# schematics.net
KiCad netlist of a schematic drawn in EAGLE
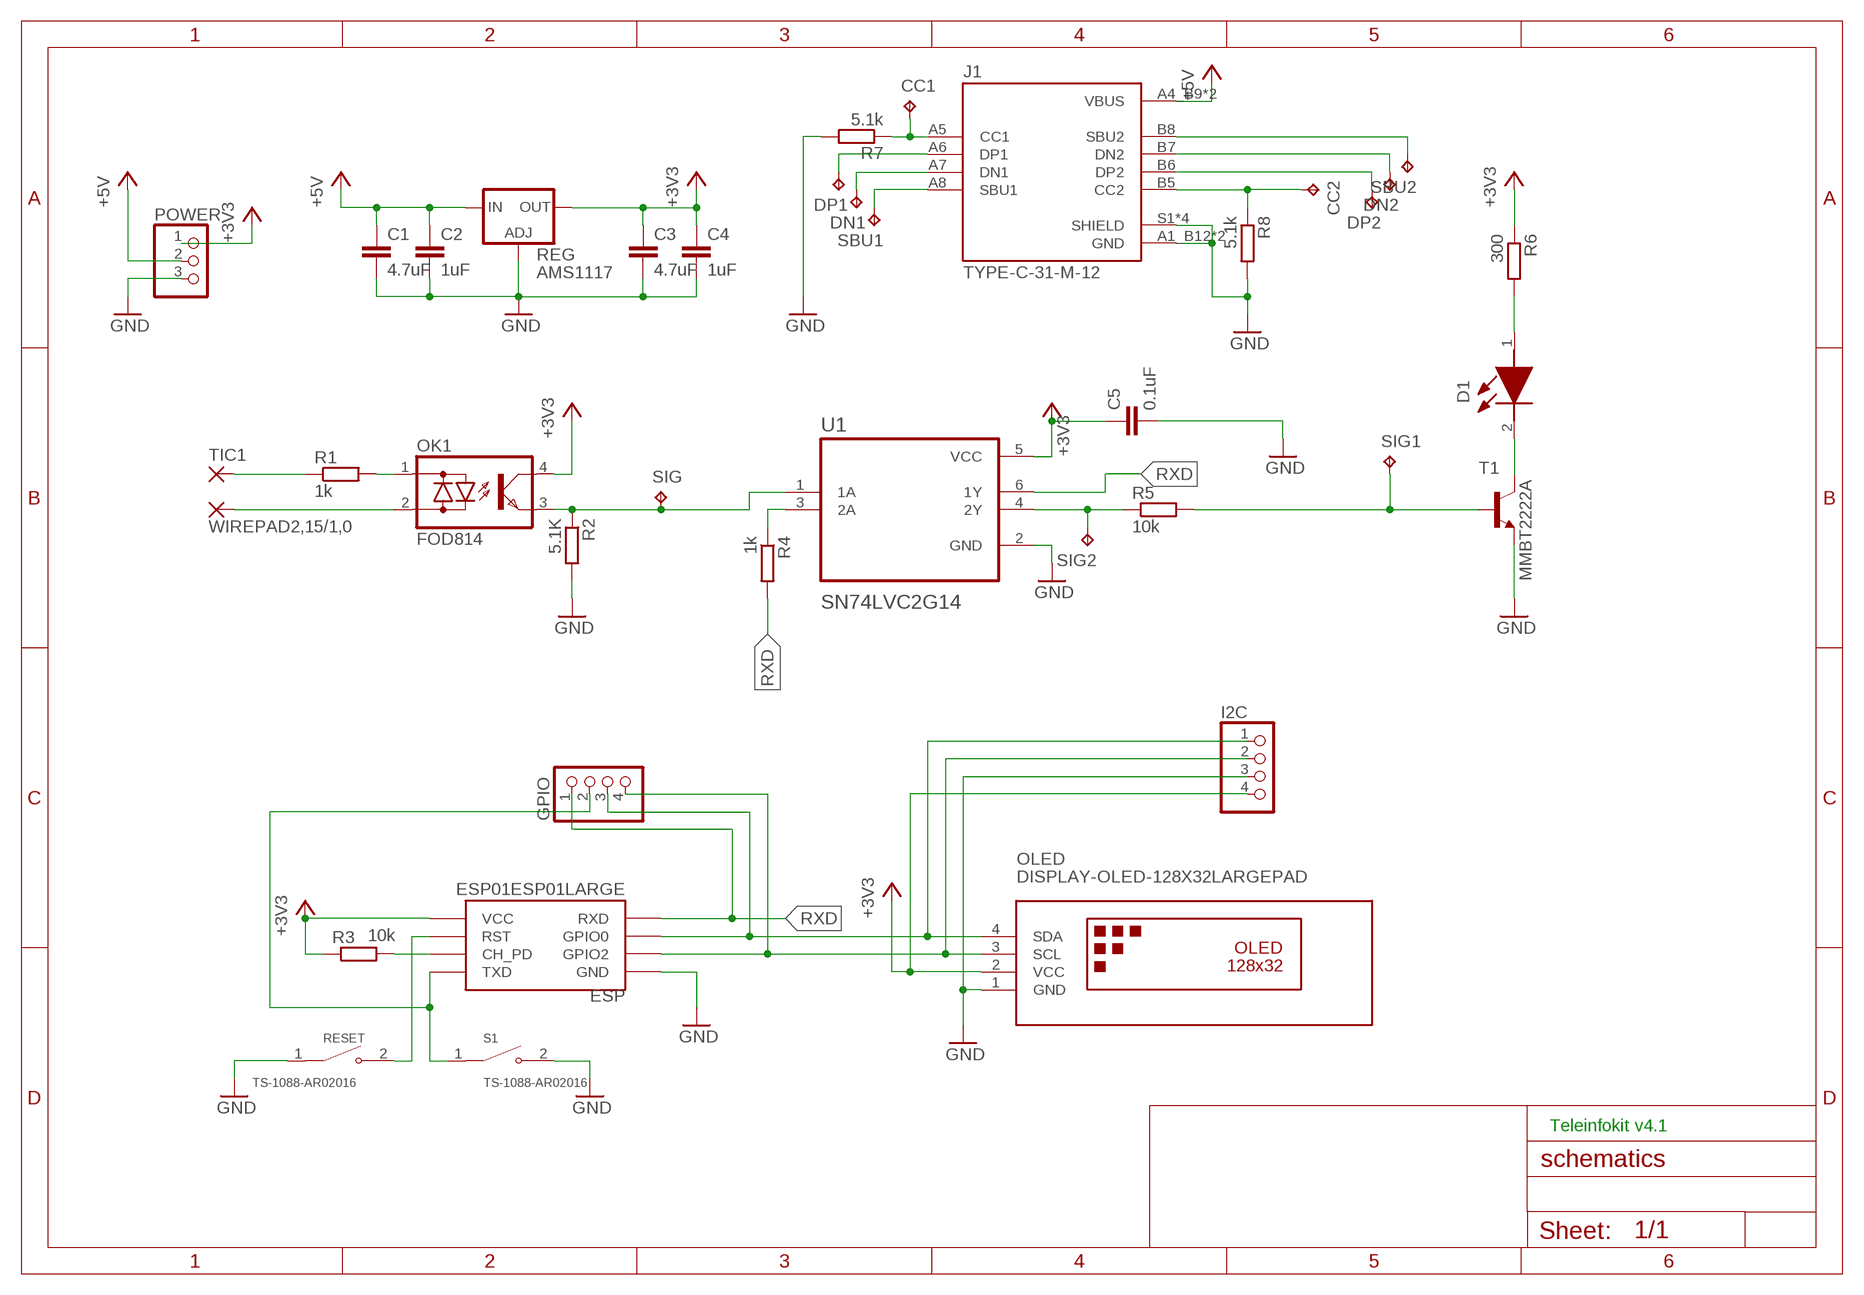
[diagram p0: schematic, sheet 1]

(export (version "E")
  (design (tool "Eeschema 10.0.6"))
  (components
    (comp (ref "C1")
      (value "4.7uF")
      (footprint "eagle-import:C0805")
      (fields (field (name "LCSC_PART") "C1779"))
      (libsource (lib "eagle-import") (part "C-EUC0805"))
    )
    (comp (ref "C2")
      (value "1uF")
      (footprint "eagle-import:C0805")
      (fields (field (name "LCSC_PART") "C28323"))
      (libsource (lib "eagle-import") (part "C-EUC0805"))
    )
    (comp (ref "C3")
      (value "4.7uF")
      (footprint "eagle-import:C0805")
      (fields (field (name "LCSC_PART") "C1779"))
      (libsource (lib "eagle-import") (part "C-EUC0805"))
    )
    (comp (ref "C4")
      (value "1uF")
      (footprint "eagle-import:C0805")
      (fields (field (name "LCSC_PART") "C28323"))
      (libsource (lib "eagle-import") (part "C-EUC0805"))
    )
    (comp (ref "C5")
      (value "0.1uF")
      (footprint "eagle-import:C0402K")
      (fields (field (name "LCSC_PART") "C1525"))
      (libsource (lib "eagle-import") (part "C-EUC0402K"))
    )
    (comp (ref "CC1")
      (value "TPB1,27")
      (footprint "eagle-import:B1,27")
      (libsource (lib "eagle-import") (part "TPB1,27"))
    )
    (comp (ref "CC2")
      (value "TPB1,27")
      (footprint "eagle-import:B1,27")
      (libsource (lib "eagle-import") (part "TPB1,27"))
    )
    (comp (ref "D1")
      (value "17-21SURC_S530-A2_TR8")
      (footprint "eagle-import:1721SURCS530A2TR8")
      (fields (field (name "ARROW_PART_NUMBER") "17-21SURC/S530-A2/TR8"))
      (libsource (lib "eagle-import") (part "17-21SURC_S530-A2_TR8"))
    )
    (comp (ref "DN1")
      (value "TPB1,27")
      (footprint "eagle-import:B1,27")
      (libsource (lib "eagle-import") (part "TPB1,27"))
    )
    (comp (ref "DN2")
      (value "TPB1,27")
      (footprint "eagle-import:B1,27")
      (libsource (lib "eagle-import") (part "TPB1,27"))
    )
    (comp (ref "DP1")
      (value "TPB1,27")
      (footprint "eagle-import:B1,27")
      (libsource (lib "eagle-import") (part "TPB1,27"))
    )
    (comp (ref "DP2")
      (value "TPB1,27")
      (footprint "eagle-import:B1,27")
      (libsource (lib "eagle-import") (part "TPB1,27"))
    )
    (comp (ref "ESP")
      (value "ESP01ESP01LARGE")
      (footprint "eagle-import:ESP01LARGE")
      (fields (field (name "LCSC_PART") "C2935984"))
      (libsource (lib "eagle-import") (part "ESP01ESP01LARGE"))
    )
    (comp (ref "GPIO")
      (value "PINHD-1X4")
      (footprint "eagle-import:1X04")
      (libsource (lib "eagle-import") (part "pinhead_325_PINHD-1X4"))
    )
    (comp (ref "I2C")
      (value "PINHD-1X4ROUNDLARGE")
      (footprint "eagle-import:1X04ROUNDLARGE")
      (libsource (lib "eagle-import") (part "PINHD-1X4ROUNDLARGE"))
    )
    (comp (ref "J1")
      (value "TYPE-C-31-M-12")
      (footprint "eagle-import:HRO_TYPE-C-31-M-12")
      (fields (field (name "MF") "HRO Electronics Co., Ltd.") (field (name "LCSC_PART") "C165948"))
      (libsource (lib "eagle-import") (part "TYPE-C-31-M-12"))
    )
    (comp (ref "OK1")
      (value "FOD814")
      (footprint "eagle-import:DIL4-SMD")
      (fields
        (field (name "MF") "VISHAY/TELEFUNKEN")
        (field (name "MPN") "SFH6206-3")
        (field (name "LCSC_PART") "C479718")
      )
      (libsource (lib "eagle-import") (part "SFH6206"))
    )
    (comp (ref "OLED")
      (value "DISPLAY-OLED-128X32LARGEPAD")
      (footprint "eagle-import:DISPLAY-OLED-128X32LARGE")
      (fields (field (name "LCSC_PART") "C2718488"))
      (libsource (lib "eagle-import") (part "DISPLAY-OLED-128X32LARGEPAD"))
    )
    (comp (ref "POWER")
      (value "PINHD-1X3")
      (footprint "eagle-import:1X03")
      (libsource (lib "eagle-import") (part "PINHD-1X3"))
    )
    (comp (ref "R1")
      (value "1k")
      (footprint "eagle-import:R0805")
      (fields (field (name "LCSC_PART") "C17513"))
      (libsource (lib "eagle-import") (part "R-EU_R0805"))
    )
    (comp (ref "R2")
      (value "5.1K")
      (footprint "eagle-import:R0603")
      (fields (field (name "LCSC_PART") "C23186"))
      (libsource (lib "eagle-import") (part "R-EU_R0603"))
    )
    (comp (ref "R3")
      (value "10k")
      (footprint "eagle-import:R0805")
      (fields (field (name "LCSC_PART") "C17414"))
      (libsource (lib "eagle-import") (part "R-EU_R0805"))
    )
    (comp (ref "R4")
      (value "1k")
      (footprint "eagle-import:R0805")
      (fields (field (name "LCSC_PART") "C17414"))
      (libsource (lib "eagle-import") (part "R-EU_R0805"))
    )
    (comp (ref "R5")
      (value "10k")
      (footprint "eagle-import:R0805")
      (fields (field (name "LCSC_PART") "C17414"))
      (libsource (lib "eagle-import") (part "R-EU_R0805"))
    )
    (comp (ref "R6")
      (value "300")
      (footprint "eagle-import:R0805")
      (fields (field (name "LCSC_PART") "C17617"))
      (libsource (lib "eagle-import") (part "R-EU_R0805"))
    )
    (comp (ref "R7")
      (value "5.1k")
      (footprint "eagle-import:R0402")
      (fields (field (name "LCSC_PART") "C25905"))
      (libsource (lib "eagle-import") (part "R-EU_R0402"))
    )
    (comp (ref "R8")
      (value "5.1k")
      (footprint "eagle-import:R0402")
      (fields (field (name "LCSC_PART") "C25905"))
      (libsource (lib "eagle-import") (part "R-EU_R0402"))
    )
    (comp (ref "REG")
      (value "AMS1117")
      (footprint "eagle-import:SOT223")
      (fields (field (name "LCSC_PART") "C6186"))
      (libsource (lib "eagle-import") (part "LD117A?S33TR"))
    )
    (comp (ref "RESET")
      (value "TS-1088-AR02016")
      (footprint "eagle-import:SW_TS-1088-AR02016")
      (fields (field (name "MF") "Xunpu") (field (name "LCSC_PART") "C720477"))
      (libsource (lib "eagle-import") (part "TS-1088-AR02016"))
    )
    (comp (ref "S1")
      (value "TS-1088-AR02016")
      (footprint "eagle-import:SW_TS-1088-AR02016")
      (fields (field (name "MF") "Xunpu") (field (name "LCSC_PART") "C720477"))
      (libsource (lib "eagle-import") (part "TS-1088-AR02016"))
    )
    (comp (ref "SBU1")
      (value "TPB1,27")
      (footprint "eagle-import:B1,27")
      (libsource (lib "eagle-import") (part "TPB1,27"))
    )
    (comp (ref "SBU2")
      (value "TPB1,27")
      (footprint "eagle-import:B1,27")
      (libsource (lib "eagle-import") (part "TPB1,27"))
    )
    (comp (ref "SIG")
      (value "TPB1,27")
      (footprint "eagle-import:B1,27")
      (libsource (lib "eagle-import") (part "TPB1,27"))
    )
    (comp (ref "SIG1")
      (value "TPB1,27")
      (footprint "eagle-import:B1,27")
      (libsource (lib "eagle-import") (part "TPB1,27"))
    )
    (comp (ref "SIG2")
      (value "TPB1,27")
      (footprint "eagle-import:B1,27")
      (libsource (lib "eagle-import") (part "TPB1,27"))
    )
    (comp (ref "T1")
      (value "MMBT2222A")
      (footprint "eagle-import:SOT23-BEC")
      (fields (field (name "LCSC_PART") "C8512"))
      (libsource (lib "eagle-import") (part "-NPN-SOT23-BECMMBT2222ALT1"))
    )
    (comp (ref "TIC1")
      (value "WIREPAD2,15/1,0")
      (footprint "eagle-import:2,15_1,0")
      (libsource (lib "eagle-import") (part "WIREPAD2,15/1,0"))
    )
    (comp (ref "TIC2")
      (value "WIREPAD2,15/1,0")
      (footprint "eagle-import:2,15_1,0")
      (libsource (lib "eagle-import") (part "WIREPAD2,15/1,0"))
    )
    (comp (ref "U1")
      (value "SN74LVC2G14")
      (footprint "eagle-import:SOT95P280X145-6N")
      (fields
        (field (name "MF") "Texas Instruments")
        (field (name "MP") "SN74LVC2G14DBVR")
        (field (name "LCSC_PART") "C12401")
      )
      (libsource (lib "eagle-import") (part "SN74LVC2G14DBVR"))
    )
  )
  (nets
    (net (code "1") (name "+3V3") (class "Default")
      (node (ref "C3") (pin "1") (pinfunction "1_1") (pintype "passive"))
      (node (ref "C4") (pin "1") (pinfunction "1_1") (pintype "passive"))
      (node (ref "C5") (pin "1") (pinfunction "1_1") (pintype "passive"))
      (node (ref "ESP") (pin "VCC") (pinfunction "VCC_VCC") (pintype "bidirectional"))
      (node (ref "I2C") (pin "4") (pinfunction "4_4") (pintype "passive"))
      (node (ref "OK1") (pin "4") (pinfunction "C_4") (pintype "passive"))
      (node (ref "OLED") (pin "2") (pinfunction "VCC_2") (pintype "power_in"))
      (node (ref "POWER") (pin "1") (pinfunction "1_1") (pintype "passive"))
      (node (ref "R3") (pin "1") (pinfunction "1_1") (pintype "passive"))
      (node (ref "R6") (pin "1") (pinfunction "1_1") (pintype "passive"))
      (node (ref "REG") (pin "4") (pinfunction "OUT_4") (pintype "passive"))
      (node (ref "U1") (pin "5") (pinfunction "VCC_5") (pintype "power_in"))
    )
    (net (code "2") (name "+5V") (class "Default")
      (node (ref "C1") (pin "1") (pinfunction "1_1") (pintype "passive"))
      (node (ref "C2") (pin "1") (pinfunction "1_1") (pintype "passive"))
      (node (ref "J1") (pin "A4_B9") (pinfunction "VBUS_A4_B9") (pintype "power_in"))
      (node (ref "J1") (pin "B4_A9") (pinfunction "VBUS_B4_A9") (pintype "power_in"))
      (node (ref "POWER") (pin "2") (pinfunction "2_2") (pintype "passive"))
      (node (ref "REG") (pin "3") (pinfunction "IN_3") (pintype "input"))
    )
    (net (code "3") (name "GND") (class "Default")
      (node (ref "C1") (pin "2") (pinfunction "2_2") (pintype "passive"))
      (node (ref "C2") (pin "2") (pinfunction "2_2") (pintype "passive"))
      (node (ref "C3") (pin "2") (pinfunction "2_2") (pintype "passive"))
      (node (ref "C4") (pin "2") (pinfunction "2_2") (pintype "passive"))
      (node (ref "C5") (pin "2") (pinfunction "2_2") (pintype "passive"))
      (node (ref "ESP") (pin "GND") (pinfunction "GND_GND") (pintype "bidirectional"))
      (node (ref "I2C") (pin "3") (pinfunction "3_3") (pintype "passive"))
      (node (ref "J1") (pin "A1_B12") (pinfunction "GND_A1_B12") (pintype "power_in"))
      (node (ref "J1") (pin "B1_A12") (pinfunction "GND_B1_A12") (pintype "power_in"))
      (node (ref "J1") (pin "S1") (pinfunction "SHIELD_S1") (pintype "passive"))
      (node (ref "J1") (pin "S2") (pinfunction "SHIELD_S2") (pintype "passive"))
      (node (ref "J1") (pin "S3") (pinfunction "SHIELD_S3") (pintype "passive"))
      (node (ref "J1") (pin "S4") (pinfunction "SHIELD_S4") (pintype "passive"))
      (node (ref "OLED") (pin "1") (pinfunction "GND_1") (pintype "power_in"))
      (node (ref "POWER") (pin "3") (pinfunction "3_3") (pintype "passive"))
      (node (ref "R2") (pin "2") (pinfunction "2_2") (pintype "passive"))
      (node (ref "R7") (pin "2") (pinfunction "2_2") (pintype "passive"))
      (node (ref "R8") (pin "2") (pinfunction "2_2") (pintype "passive"))
      (node (ref "REG") (pin "1") (pinfunction "ADJ_1") (pintype "input"))
      (node (ref "RESET") (pin "1") (pinfunction "1_1") (pintype "passive"))
      (node (ref "S1") (pin "2") (pinfunction "2_2") (pintype "passive"))
      (node (ref "T1") (pin "E") (pinfunction "E_E") (pintype "passive"))
      (node (ref "U1") (pin "2") (pinfunction "GND_2") (pintype "power_in"))
    )
    (net (code "4") (name "Net-(D1-A)") (class "Default")
      (node (ref "D1") (pin "1") (pinfunction "A_1") (pintype "bidirectional"))
      (node (ref "R6") (pin "2") (pinfunction "2_2") (pintype "passive"))
    )
    (net (code "5") (name "Net-(D1-K)") (class "Default")
      (node (ref "D1") (pin "2") (pinfunction "K_2") (pintype "bidirectional"))
      (node (ref "T1") (pin "C") (pinfunction "C_C") (pintype "passive"))
    )
    (net (code "6") (name "Net-(ESP-PadCH_PD)") (class "Default")
      (node (ref "ESP") (pin "CH_PD") (pinfunction "CH_PD_CH_PD") (pintype "bidirectional"))
      (node (ref "R3") (pin "2") (pinfunction "2_2") (pintype "passive"))
    )
    (net (code "7") (name "Net-(ESP-PadRST)") (class "Default")
      (node (ref "ESP") (pin "RST") (pinfunction "RST_RST") (pintype "bidirectional"))
      (node (ref "RESET") (pin "2") (pinfunction "2_2") (pintype "passive"))
    )
    (net (code "8") (name "Net-(ESP-TXD)") (class "Default")
      (node (ref "ESP") (pin "TX") (pinfunction "TXD_TX") (pintype "bidirectional"))
      (node (ref "GPIO") (pin "2") (pinfunction "2_2") (pintype "passive"))
      (node (ref "S1") (pin "1") (pinfunction "1_1") (pintype "passive"))
    )
    (net (code "9") (name "Net-(J1-CC1)") (class "Default")
      (node (ref "CC1") (pin "TP") (pinfunction "TP_TP") (pintype "input"))
      (node (ref "J1") (pin "A5") (pinfunction "CC1_A5") (pintype "bidirectional"))
      (node (ref "R7") (pin "1") (pinfunction "1_1") (pintype "passive"))
    )
    (net (code "10") (name "Net-(J1-CC2)") (class "Default")
      (node (ref "CC2") (pin "TP") (pinfunction "TP_TP") (pintype "input"))
      (node (ref "J1") (pin "B5") (pinfunction "CC2_B5") (pintype "bidirectional"))
      (node (ref "R8") (pin "1") (pinfunction "1_1") (pintype "passive"))
    )
    (net (code "11") (name "Net-(J1-DN1)") (class "Default")
      (node (ref "DN1") (pin "TP") (pinfunction "TP_TP") (pintype "input"))
      (node (ref "J1") (pin "A7") (pinfunction "DN1_A7") (pintype "bidirectional"))
    )
    (net (code "12") (name "Net-(J1-DN2)") (class "Default")
      (node (ref "DN2") (pin "TP") (pinfunction "TP_TP") (pintype "input"))
      (node (ref "J1") (pin "B7") (pinfunction "DN2_B7") (pintype "bidirectional"))
    )
    (net (code "13") (name "Net-(J1-DP1)") (class "Default")
      (node (ref "DP1") (pin "TP") (pinfunction "TP_TP") (pintype "input"))
      (node (ref "J1") (pin "A6") (pinfunction "DP1_A6") (pintype "bidirectional"))
    )
    (net (code "14") (name "Net-(J1-DP2)") (class "Default")
      (node (ref "DP2") (pin "TP") (pinfunction "TP_TP") (pintype "input"))
      (node (ref "J1") (pin "B6") (pinfunction "DP2_B6") (pintype "bidirectional"))
    )
    (net (code "15") (name "Net-(J1-SBU1)") (class "Default")
      (node (ref "J1") (pin "A8") (pinfunction "SBU1_A8") (pintype "bidirectional"))
      (node (ref "SBU1") (pin "TP") (pinfunction "TP_TP") (pintype "input"))
    )
    (net (code "16") (name "Net-(J1-SBU2)") (class "Default")
      (node (ref "J1") (pin "B8") (pinfunction "SBU2_B8") (pintype "bidirectional"))
      (node (ref "SBU2") (pin "TP") (pinfunction "TP_TP") (pintype "input"))
    )
    (net (code "17") (name "Net-(OK1-AC1)") (class "Default")
      (node (ref "OK1") (pin "1") (pinfunction "AC1_1") (pintype "passive"))
      (node (ref "R1") (pin "2") (pinfunction "2_2") (pintype "passive"))
    )
    (net (code "18") (name "Net-(OK1-AC2)") (class "Default")
      (node (ref "OK1") (pin "2") (pinfunction "AC2_2") (pintype "passive"))
      (node (ref "TIC2") (pin "1") (pinfunction "P_1") (pintype "passive"))
    )
    (net (code "19") (name "Net-(OK1-E)") (class "Default")
      (node (ref "OK1") (pin "3") (pinfunction "E_3") (pintype "passive"))
      (node (ref "R2") (pin "1") (pinfunction "1_1") (pintype "passive"))
      (node (ref "SIG") (pin "TP") (pinfunction "TP_TP") (pintype "input"))
      (node (ref "U1") (pin "1") (pinfunction "1A_1") (pintype "input"))
    )
    (net (code "20") (name "Net-(OLED-SCL)") (class "Default")
      (node (ref "ESP") (pin "GPIO2") (pinfunction "GPIO2_GPIO2") (pintype "bidirectional"))
      (node (ref "GPIO") (pin "4") (pinfunction "4_4") (pintype "passive"))
      (node (ref "I2C") (pin "2") (pinfunction "2_2") (pintype "passive"))
      (node (ref "OLED") (pin "3") (pinfunction "SCL_3") (pintype "bidirectional"))
    )
    (net (code "21") (name "Net-(OLED-SDA)") (class "Default")
      (node (ref "ESP") (pin "GPIO0") (pinfunction "GPIO0_GPIO0") (pintype "bidirectional"))
      (node (ref "GPIO") (pin "3") (pinfunction "3_3") (pintype "passive"))
      (node (ref "I2C") (pin "1") (pinfunction "1_1") (pintype "passive"))
      (node (ref "OLED") (pin "4") (pinfunction "SDA_4") (pintype "bidirectional"))
    )
    (net (code "22") (name "Net-(R5-Pad2)") (class "Default")
      (node (ref "R5") (pin "2") (pinfunction "2_2") (pintype "passive"))
      (node (ref "SIG1") (pin "TP") (pinfunction "TP_TP") (pintype "input"))
      (node (ref "T1") (pin "B") (pinfunction "B_B") (pintype "passive"))
    )
    (net (code "23") (name "Net-(TIC1-P)") (class "Default")
      (node (ref "R1") (pin "1") (pinfunction "1_1") (pintype "passive"))
      (node (ref "TIC1") (pin "1") (pinfunction "P_1") (pintype "passive"))
    )
    (net (code "24") (name "Net-(U1-2A)") (class "Default")
      (node (ref "R4") (pin "1") (pinfunction "1_1") (pintype "passive"))
      (node (ref "U1") (pin "3") (pinfunction "2A_3") (pintype "input"))
    )
    (net (code "25") (name "Net-(U1-2Y)") (class "Default")
      (node (ref "R5") (pin "1") (pinfunction "1_1") (pintype "passive"))
      (node (ref "SIG2") (pin "TP") (pinfunction "TP_TP") (pintype "input"))
      (node (ref "U1") (pin "4") (pinfunction "2Y_4") (pintype "output"))
    )
    (net (code "26") (name "RXD") (class "Default")
      (node (ref "ESP") (pin "RX") (pinfunction "RXD_RX") (pintype "bidirectional"))
      (node (ref "GPIO") (pin "1") (pinfunction "1_1") (pintype "passive"))
      (node (ref "R4") (pin "2") (pinfunction "2_2") (pintype "passive"))
      (node (ref "U1") (pin "6") (pinfunction "1Y_6") (pintype "output"))
    )
  )
)
